# Buck.net
KiCad netlist of a schematic drawn in Altium Designer
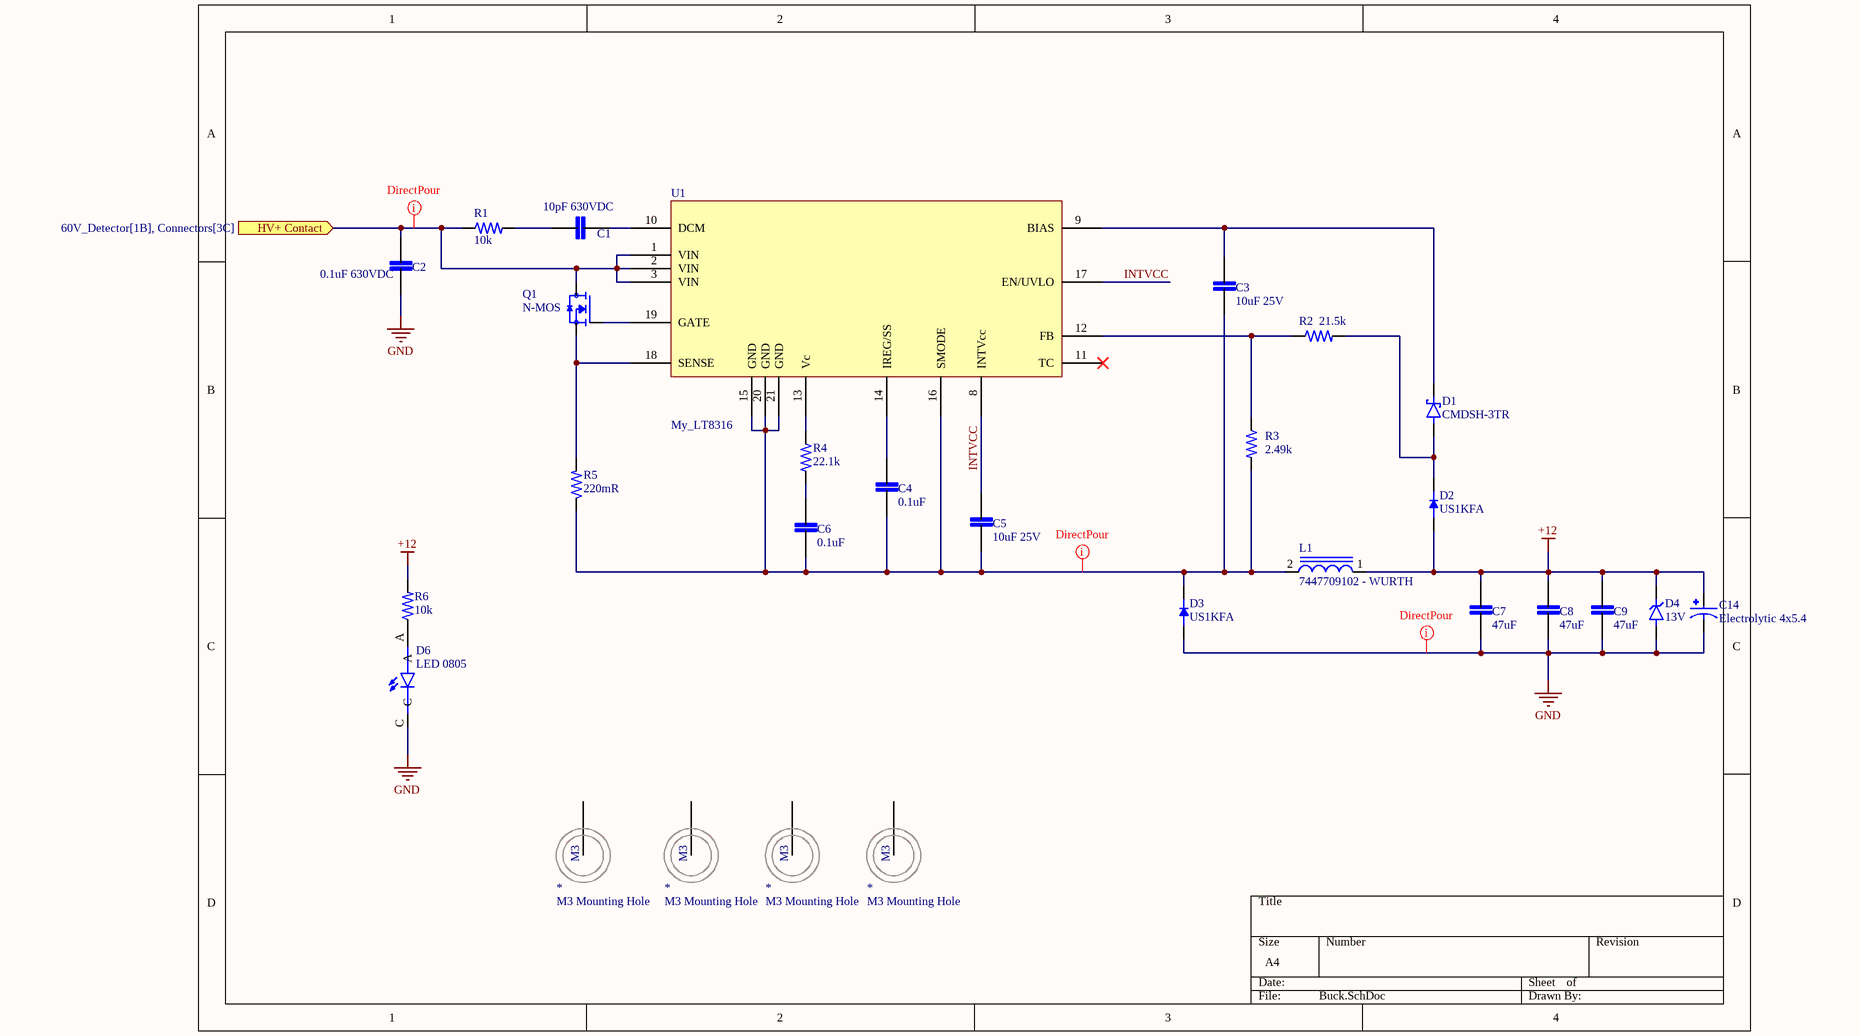
[diagram p0: Buck.SchDoc]

(export (version "E")
  (design (tool "Eeschema 10.0.6"))
  (components
    (comp (ref "*")
      (value "M3 Mounting Hole")
      (footprint "M3 - Mounting Hole")
      (libsource (lib "Connectors Through Hole") (part "M3 Mounting Hole"))
    )
    (comp (ref "C1")
      (value "10pF 630VDC")
      (footprint "0805")
      (fields (field (name "MP") "LD051A121KAB2A") (field (name "MF") "AVX"))
      (libsource (lib "") (part "0805_Capacitor_2"))
    )
    (comp (ref "C2")
      (value "0.1uF 630VDC")
      (footprint "1812")
      (fields (field (name "MP") "LD051A121KAB2A") (field (name "MF") "AVX"))
      (libsource (lib "SMD_Generic") (part "1812_Capacitor"))
    )
    (comp (ref "C3")
      (value "10uF 25V")
      (footprint "0805")
      (fields (field (name "MP") "LD051A121KAB2A") (field (name "MF") "AVX"))
      (libsource (lib "") (part "0805_Capacitor_1"))
    )
    (comp (ref "C4")
      (value "0.1uF")
      (footprint "0805")
      (fields (field (name "MP") "LD051A121KAB2A") (field (name "MF") "AVX"))
      (libsource (lib "SMD_Generic") (part "0805_Capacitor"))
    )
    (comp (ref "C5")
      (value "10uF 25V")
      (footprint "0805")
      (fields (field (name "MP") "LD051A121KAB2A") (field (name "MF") "AVX"))
      (libsource (lib "") (part "0805_Capacitor_1"))
    )
    (comp (ref "C6")
      (value "0.1uF")
      (footprint "0805")
      (fields (field (name "MP") "LD051A121KAB2A") (field (name "MF") "AVX"))
      (libsource (lib "SMD_Generic") (part "0805_Capacitor"))
    )
    (comp (ref "C7")
      (value "47uF")
      (footprint "0805")
      (fields (field (name "MP") "LD051A121KAB2A") (field (name "MF") "AVX"))
      (libsource (lib "SMD_Generic") (part "0805_Capacitor"))
    )
    (comp (ref "C8")
      (value "47uF")
      (footprint "0805")
      (fields (field (name "MP") "LD051A121KAB2A") (field (name "MF") "AVX"))
      (libsource (lib "SMD_Generic") (part "0805_Capacitor"))
    )
    (comp (ref "C9")
      (value "47uF")
      (footprint "0805")
      (fields (field (name "MP") "LD051A121KAB2A") (field (name "MF") "AVX"))
      (libsource (lib "SMD_Generic") (part "0805_Capacitor"))
    )
    (comp (ref "C14")
      (value "Electrolytic 4x5.4")
      (footprint "Capacitors SMD:Electrolytic 4x5.4")
      (fields (field (name "MF") "Panasonic") (field (name "MP") "EEE-HA1E100WR"))
      (libsource (lib "Capacitors SMD") (part "Electrolytic 4x5.4"))
    )
    (comp (ref "D1")
      (value "CMDSH-3TR")
      (footprint "Diodes SMD:SOD-323")
      (description "Diode Schottky 30V 100mA Surface Mount SOD-323")
      (fields (field (name "MP") "CMDSH-3 TR") (field (name "MF") "Central Semiconductor"))
      (libsource (lib "Diodes SMD") (part "CMDSH-3TR"))
    )
    (comp (ref "D2")
      (value "US1KFA")
      (footprint "SOD123")
      (fields (field (name "MF") "Diodes Inc.") (field (name "MP") "1N4148W-7-F"))
      (libsource (lib "Diodes SMD") (part "SOD123 - Rectifier Diode"))
    )
    (comp (ref "D3")
      (value "US1KFA")
      (footprint "SOD123")
      (fields (field (name "MF") "Diodes Inc.") (field (name "MP") "1N4148W-7-F"))
      (libsource (lib "Diodes SMD") (part "SOD123 - Rectifier Diode"))
    )
    (comp (ref "D4")
      (value "13V")
      (footprint "SOD123")
      (fields (field (name "MP") "1SMA5926") (field (name "MF") "Taiwan Semiconductor"))
      (libsource (lib "Diodes SMD") (part "SOD123 - Zener Diode"))
    )
    (comp (ref "D6")
      (value "LED 0805")
      (footprint "LED 0805")
      (description "LED Uni-Color Green 4-Pin Chip 0805 T/R")
      (fields (field (name "MP") "597-3305-607F"))
      (libsource (lib "LEDs SMD") (part "LED 0805"))
    )
    (comp (ref "L1")
      (value "7447709102 - WURTH")
      (footprint "7447709102 - WURTH")
      (description "1000uH - 900mA")
      (fields (field (name "MF") "Bourns") (field (name "DIGI-KEY_PART_NUMBER") "SRR1260-680MCT-ND"))
      (libsource (lib "Inductors SMD") (part "7447709102 - WURTH"))
    )
    (comp (ref "Q1")
      (value "N-MOS")
      (footprint "DPAK - MOSFET")
      (description "D-PAK")
      (fields (field (name "MP") "AO3402") (field (name "MF") "Alpha &"))
      (libsource (lib "Mosfet SMD") (part "N-MOS"))
    )
    (comp (ref "R1")
      (value "10k")
      (footprint "0805")
      (fields
        (field (name "MP") "2-2176053-0")
        (field (name "TOLERANCE") "1%")
        (field (name "MF") "TE Connectivity")
      )
      (libsource (lib "SMD_Generic") (part "0805_Resistor"))
    )
    (comp (ref "R2")
      (value "21.5k")
      (footprint "0805")
      (fields
        (field (name "MP") "2-2176053-0")
        (field (name "TOLERANCE") "1%")
        (field (name "MF") "TE Connectivity")
      )
      (libsource (lib "SMD_Generic") (part "0805_Resistor"))
    )
    (comp (ref "R3")
      (value "2.49k")
      (footprint "0805")
      (fields
        (field (name "MP") "2-2176053-0")
        (field (name "TOLERANCE") "1%")
        (field (name "MF") "TE Connectivity")
      )
      (libsource (lib "SMD_Generic") (part "0805_Resistor"))
    )
    (comp (ref "R4")
      (value "22.1k")
      (footprint "0805")
      (fields
        (field (name "MP") "2-2176053-0")
        (field (name "TOLERANCE") "1%")
        (field (name "MF") "TE Connectivity")
      )
      (libsource (lib "SMD_Generic") (part "0805_Resistor"))
    )
    (comp (ref "R5")
      (value "220mR")
      (footprint "0805")
      (fields
        (field (name "MP") "2-2176053-0")
        (field (name "TOLERANCE") "1%")
        (field (name "MF") "TE Connectivity")
      )
      (libsource (lib "SMD_Generic") (part "0805_Resistor"))
    )
    (comp (ref "R6")
      (value "10k")
      (footprint "0805")
      (fields
        (field (name "MP") "2-2176053-0")
        (field (name "TOLERANCE") "1%")
        (field (name "MF") "TE Connectivity")
      )
      (libsource (lib "SMD_Generic") (part "0805_Resistor"))
    )
    (comp (ref "U1")
      (value "My_LT8316")
      (footprint "IC_LT8316EFE#PBF")
      (libsource (lib "HV_Indicator") (part "My_LT8316"))
    )
  )
  (nets
    (net (code "1") (name "+12") (class "Default")
      (node (ref "C14") (pin "1") (pinfunction "1_1") (pintype "passive"))
      (node (ref "C7") (pin "2") (pinfunction "2_2") (pintype "passive"))
      (node (ref "C8") (pin "2") (pinfunction "2_2") (pintype "passive"))
      (node (ref "C9") (pin "2") (pinfunction "2_2") (pintype "passive"))
      (node (ref "D2") (pin "1") (pinfunction "K_1") (pintype "passive"))
      (node (ref "D4") (pin "1") (pinfunction "K_1") (pintype "passive"))
      (node (ref "L1") (pin "1") (pinfunction "1_1") (pintype "passive"))
      (node (ref "R6") (pin "2") (pinfunction "2_2") (pintype "passive"))
    )
    (net (code "2") (name "/HV+ Contact") (class "Default")
      (node (ref "C2") (pin "2") (pinfunction "2_2") (pintype "passive"))
      (node (ref "Q1") (pin "3") (pinfunction "D_3") (pintype "passive"))
      (node (ref "R1") (pin "1") (pinfunction "1_1") (pintype "passive"))
      (node (ref "U1") (pin "1") (pinfunction "VIN_1") (pintype "passive"))
      (node (ref "U1") (pin "2") (pinfunction "VIN_2") (pintype "passive"))
      (node (ref "U1") (pin "3") (pinfunction "VIN_3") (pintype "passive"))
    )
    (net (code "3") (name "/INTVCC") (class "Default")
      (node (ref "C5") (pin "1") (pinfunction "1_1") (pintype "passive"))
      (node (ref "U1") (pin "17") (pinfunction "EN/UVLO_17") (pintype "passive"))
      (node (ref "U1") (pin "8") (pinfunction "INTVcc_8") (pintype "passive"))
    )
    (net (code "4") (name "GND") (class "Default")
      (node (ref "C14") (pin "2") (pinfunction "2_2") (pintype "passive"))
      (node (ref "C2") (pin "1") (pinfunction "1_1") (pintype "passive"))
      (node (ref "C7") (pin "1") (pinfunction "1_1") (pintype "passive"))
      (node (ref "C8") (pin "1") (pinfunction "1_1") (pintype "passive"))
      (node (ref "C9") (pin "1") (pinfunction "1_1") (pintype "passive"))
      (node (ref "D3") (pin "1") (pinfunction "K_1") (pintype "passive"))
      (node (ref "D4") (pin "2") (pinfunction "A_2") (pintype "passive"))
      (node (ref "D6") (pin "C") (pinfunction "C_C") (pintype "passive"))
    )
    (net (code "5") (name "Net-(C1-Pad1)") (class "Default")
      (node (ref "C1") (pin "1") (pinfunction "1_1") (pintype "passive"))
      (node (ref "R1") (pin "2") (pinfunction "2_2") (pintype "passive"))
    )
    (net (code "6") (name "Net-(C6-Pad2)") (class "Default")
      (node (ref "C6") (pin "2") (pinfunction "2_2") (pintype "passive"))
      (node (ref "R4") (pin "2") (pinfunction "2_2") (pintype "passive"))
    )
    (net (code "7") (name "Net-(D2-A)") (class "Default")
      (node (ref "D1") (pin "A") (pinfunction "A_A") (pintype "passive"))
      (node (ref "D2") (pin "2") (pinfunction "A_2") (pintype "passive"))
      (node (ref "R2") (pin "2") (pinfunction "2_2") (pintype "passive"))
    )
    (net (code "8") (name "Net-(D3-A)") (class "Default")
      (node (ref "C3") (pin "2") (pinfunction "2_2") (pintype "passive"))
      (node (ref "C4") (pin "1") (pinfunction "1_1") (pintype "passive"))
      (node (ref "C5") (pin "2") (pinfunction "2_2") (pintype "passive"))
      (node (ref "C6") (pin "1") (pinfunction "1_1") (pintype "passive"))
      (node (ref "D3") (pin "2") (pinfunction "A_2") (pintype "passive"))
      (node (ref "L1") (pin "2") (pinfunction "2_2") (pintype "passive"))
      (node (ref "R3") (pin "2") (pinfunction "2_2") (pintype "passive"))
      (node (ref "R5") (pin "1") (pinfunction "1_1") (pintype "passive"))
      (node (ref "U1") (pin "15") (pinfunction "GND_15") (pintype "passive"))
      (node (ref "U1") (pin "16") (pinfunction "SMODE_16") (pintype "passive"))
      (node (ref "U1") (pin "20") (pinfunction "GND_20") (pintype "passive"))
      (node (ref "U1") (pin "21") (pinfunction "GND_21") (pintype "passive"))
    )
    (net (code "9") (name "Net-(D6-PadA)") (class "Default")
      (node (ref "D6") (pin "A") (pinfunction "A_A") (pintype "passive"))
      (node (ref "R6") (pin "1") (pinfunction "1_1") (pintype "passive"))
    )
    (net (code "10") (name "Net-(Q1-G)") (class "Default")
      (node (ref "Q1") (pin "1") (pinfunction "G_1") (pintype "passive"))
      (node (ref "U1") (pin "19") (pinfunction "GATE_19") (pintype "passive"))
    )
    (net (code "11") (name "Net-(Q1-S)") (class "Default")
      (node (ref "Q1") (pin "2") (pinfunction "S_2") (pintype "passive"))
      (node (ref "R5") (pin "2") (pinfunction "2_2") (pintype "passive"))
      (node (ref "U1") (pin "18") (pinfunction "SENSE_18") (pintype "passive"))
    )
    (net (code "12") (name "Net-(U1-BIAS)") (class "Default")
      (node (ref "C3") (pin "1") (pinfunction "1_1") (pintype "passive"))
      (node (ref "D1") (pin "C") (pinfunction "C_C") (pintype "passive"))
      (node (ref "U1") (pin "9") (pinfunction "BIAS_9") (pintype "passive"))
    )
    (net (code "13") (name "Net-(U1-DCM)") (class "Default")
      (node (ref "C1") (pin "2") (pinfunction "2_2") (pintype "passive"))
      (node (ref "U1") (pin "10") (pinfunction "DCM_10") (pintype "passive"))
    )
    (net (code "14") (name "Net-(U1-FB)") (class "Default")
      (node (ref "R2") (pin "1") (pinfunction "1_1") (pintype "passive"))
      (node (ref "R3") (pin "1") (pinfunction "1_1") (pintype "passive"))
      (node (ref "U1") (pin "12") (pinfunction "FB_12") (pintype "passive"))
    )
    (net (code "15") (name "Net-(U1-IREG{slash}SS)") (class "Default")
      (node (ref "C4") (pin "2") (pinfunction "2_2") (pintype "passive"))
      (node (ref "U1") (pin "14") (pinfunction "IREG/SS_14") (pintype "passive"))
    )
    (net (code "16") (name "Net-(U1-Vc)") (class "Default")
      (node (ref "R4") (pin "1") (pinfunction "1_1") (pintype "passive"))
      (node (ref "U1") (pin "13") (pinfunction "Vc_13") (pintype "passive"))
    )
    (net (code "17") (name "unconnected-(*-M3-Pad1)") (class "Default")
      (node (ref "*") (pin "1") (pinfunction "M3_1") (pintype "passive"))
    )
    (net (code "18") (name "unconnected-(*-M3-Pad1)_1") (class "Default")
      (node (ref "*") (pin "1") (pinfunction "M3_1") (pintype "passive"))
    )
    (net (code "19") (name "unconnected-(*-M3-Pad1)_2") (class "Default")
      (node (ref "*") (pin "1") (pinfunction "M3_1") (pintype "passive"))
    )
    (net (code "20") (name "unconnected-(*-M3-Pad1)_3") (class "Default")
      (node (ref "*") (pin "1") (pinfunction "M3_1") (pintype "passive"))
    )
    (net (code "21") (name "unconnected-(U1-TC-Pad11)") (class "Default")
      (node (ref "U1") (pin "11") (pinfunction "TC_11") (pintype "passive+no_connect"))
    )
  )
)
